# untitled.net
KiCad netlist of a schematic drawn in EAGLE
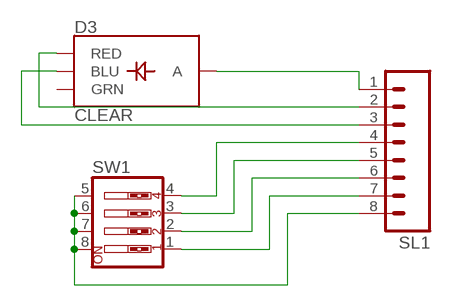
[diagram p0: schematic, sheet 1]

(export (version "E")
  (design (tool "Eeschema 10.0.6"))
  (components
    (comp (ref "D3")
      (value "CLEAR")
      (footprint "eagle-import:LED-RGB-THRU")
      (libsource (lib "eagle-import") (part "LED-RGB-CACLEAR"))
    )
    (comp (ref "SL1")
      (value "M08")
      (footprint "eagle-import:08P")
      (libsource (lib "eagle-import") (part "M08"))
    )
    (comp (ref "SW1")
      (value "SW_DIP-4")
      (footprint "eagle-import:EDG-04")
      (libsource (lib "eagle-import") (part "SW_DIP-4"))
    )
  )
  (nets
    (net (code "1") (name "Net-(D3-A)") (class "Default")
      (node (ref "D3") (pin "2") (pinfunction "A_2") (pintype "bidirectional"))
      (node (ref "SL1") (pin "1") (pinfunction "1_1") (pintype "passive"))
    )
    (net (code "2") (name "Net-(D3-BLU)") (class "Default")
      (node (ref "D3") (pin "4") (pinfunction "BLU_4") (pintype "bidirectional"))
      (node (ref "SL1") (pin "3") (pinfunction "3_3") (pintype "passive"))
    )
    (net (code "3") (name "Net-(D3-RED)") (class "Default")
      (node (ref "D3") (pin "1") (pinfunction "RED_1") (pintype "bidirectional"))
      (node (ref "SL1") (pin "2") (pinfunction "2_2") (pintype "passive"))
    )
    (net (code "4") (name "Net-(SL1-Pad4)") (class "Default")
      (node (ref "SL1") (pin "4") (pinfunction "4_4") (pintype "passive"))
      (node (ref "SW1") (pin "4") (pinfunction "4_4") (pintype "passive"))
    )
    (net (code "5") (name "Net-(SL1-Pad5)") (class "Default")
      (node (ref "SL1") (pin "5") (pinfunction "5_5") (pintype "passive"))
      (node (ref "SW1") (pin "3") (pinfunction "3_3") (pintype "passive"))
    )
    (net (code "6") (name "Net-(SL1-Pad6)") (class "Default")
      (node (ref "SL1") (pin "6") (pinfunction "6_6") (pintype "passive"))
      (node (ref "SW1") (pin "2") (pinfunction "2_2") (pintype "passive"))
    )
    (net (code "7") (name "Net-(SL1-Pad7)") (class "Default")
      (node (ref "SL1") (pin "7") (pinfunction "7_7") (pintype "passive"))
      (node (ref "SW1") (pin "1") (pinfunction "1_1") (pintype "passive"))
    )
    (net (code "8") (name "Net-(SL1-Pad8)") (class "Default")
      (node (ref "SL1") (pin "8") (pinfunction "8_8") (pintype "passive"))
      (node (ref "SW1") (pin "5") (pinfunction "5_5") (pintype "passive"))
      (node (ref "SW1") (pin "6") (pinfunction "6_6") (pintype "passive"))
      (node (ref "SW1") (pin "7") (pinfunction "7_7") (pintype "passive"))
      (node (ref "SW1") (pin "8") (pinfunction "8_8") (pintype "passive"))
    )
    (net (code "9") (name "unconnected-(D3-GRN-Pad3)") (class "Default")
      (node (ref "D3") (pin "3") (pinfunction "GRN_3") (pintype "bidirectional"))
    )
  )
)
